# XD.net
KiCad netlist of a schematic drawn in Altium Designer
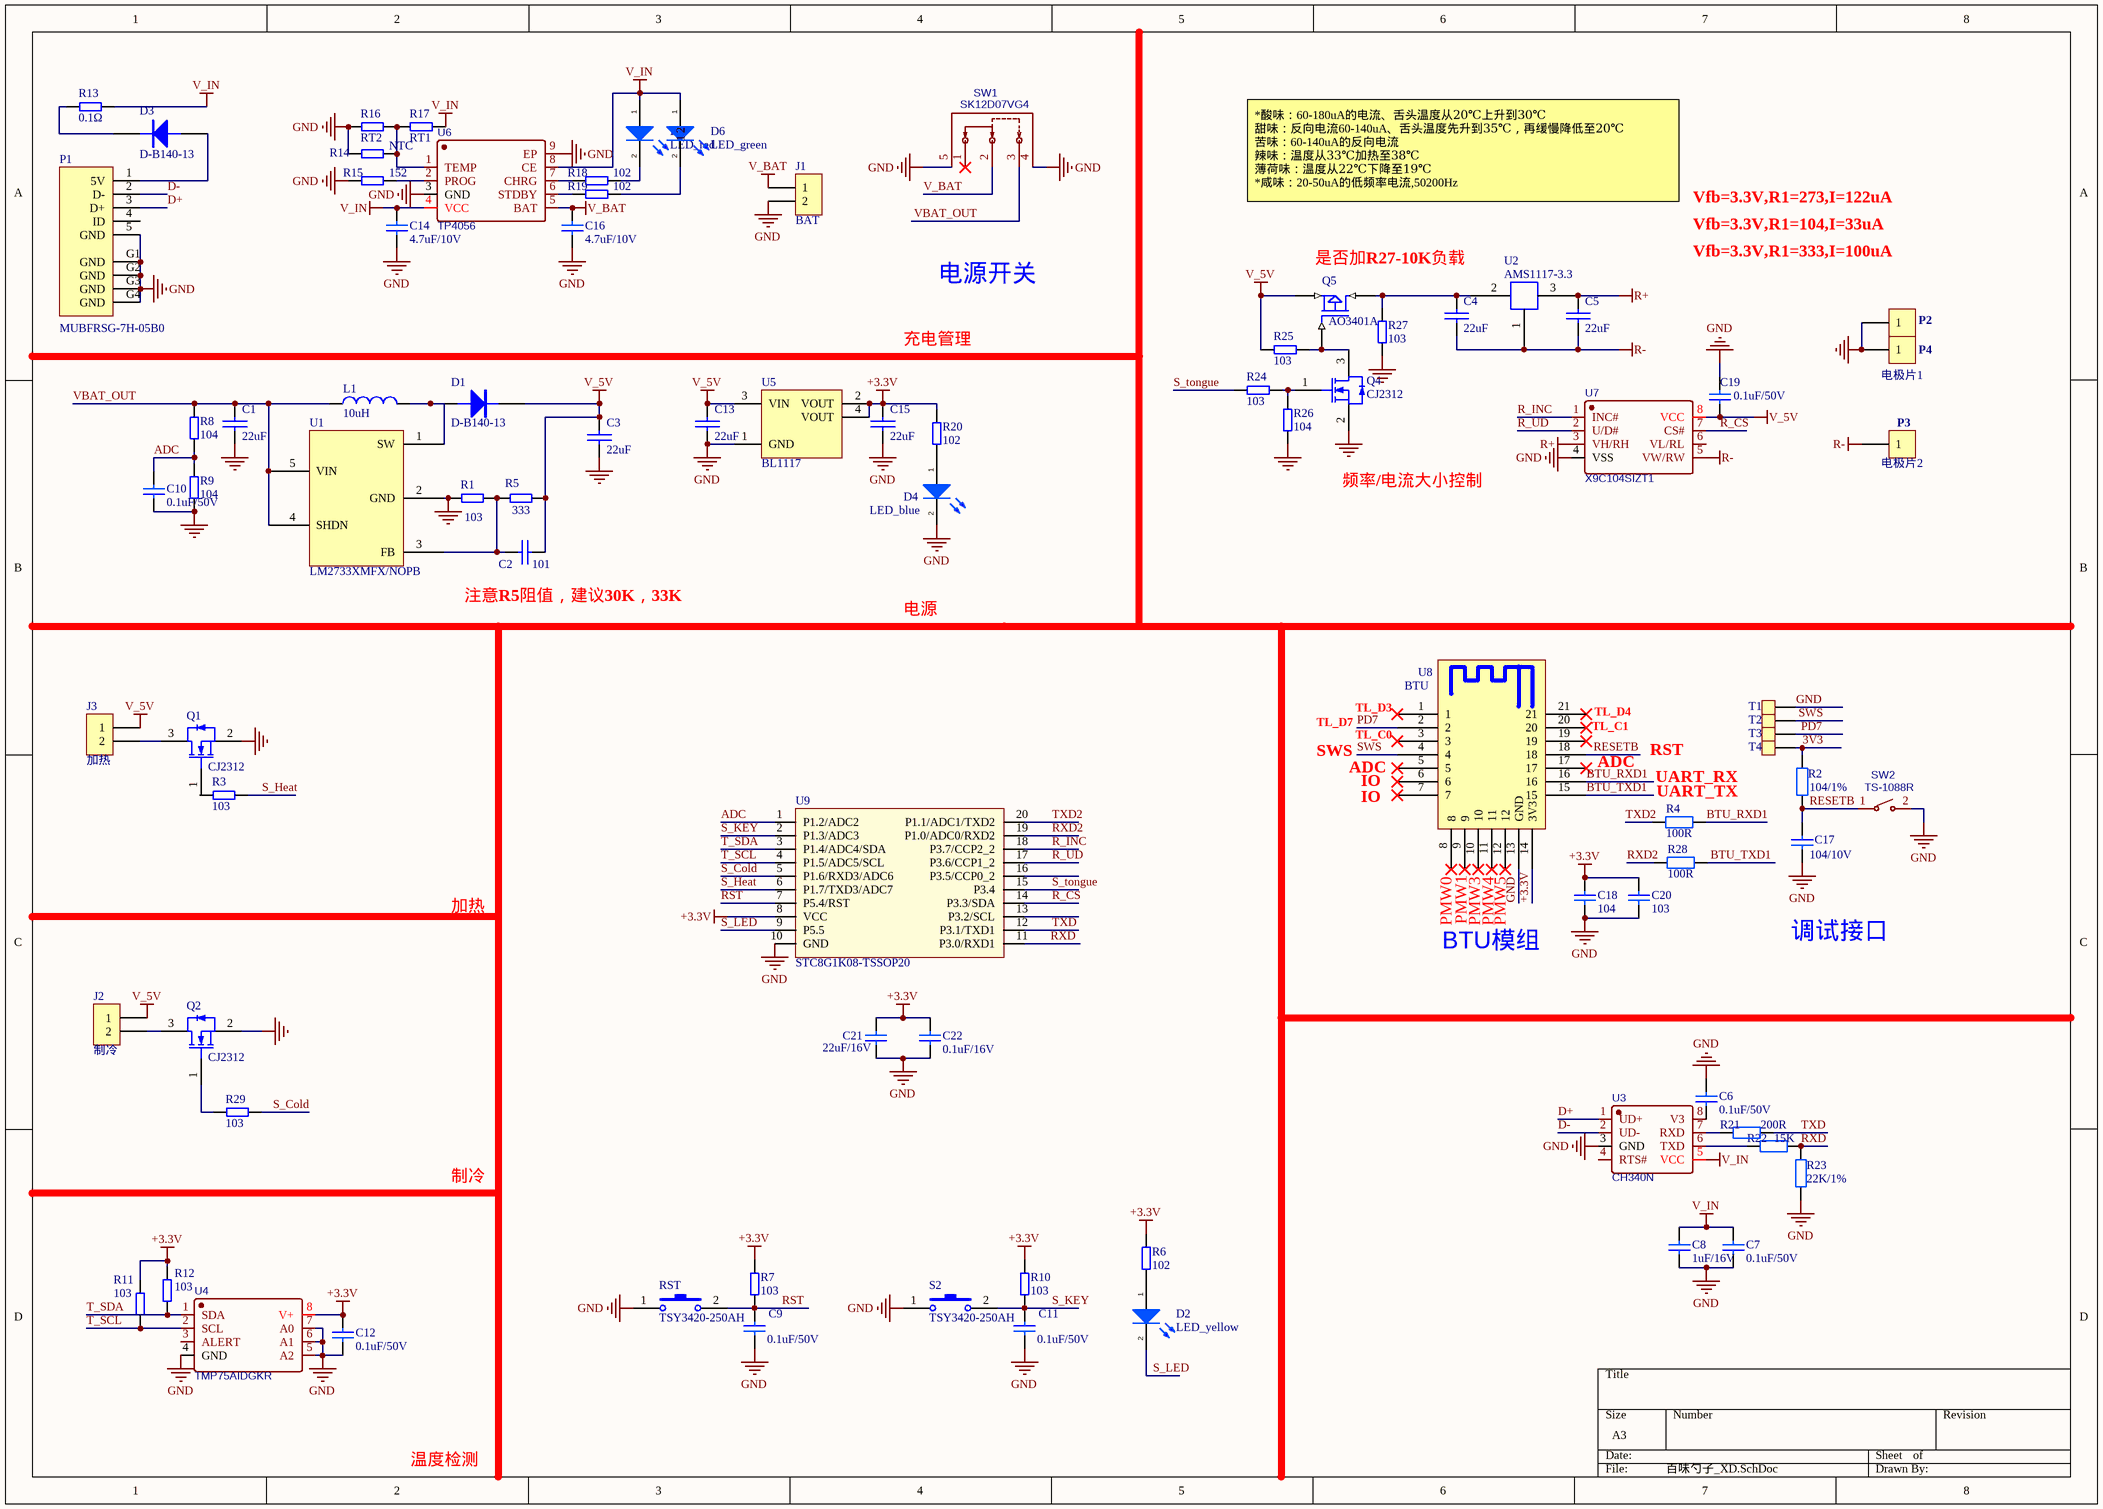
[diagram p0: 百味勺子_XD.SchDoc]

(export (version "E")
  (design (tool "Eeschema 10.0.6"))
  (components
    (comp (ref "C1") (value "22uF") (footprint "C1206") (libsource (lib "altium-import") (part "root_0_C1_")))
    (comp (ref "C2")
      (value "101")
      (footprint "C0603")
      (description "Capacitor")
      (libsource (lib "先锋器件封装库") (part "CAP"))
    )
    (comp (ref "C3") (value "22uF") (footprint "C1206") (libsource (lib "altium-import") (part "root_0_C1_")))
    (comp (ref "C4") (value "22uF") (footprint "C1206") (libsource (lib "altium-import") (part "root_0_C1_")))
    (comp (ref "C5") (value "22uF") (footprint "C1206") (libsource (lib "altium-import") (part "root_0_C1_")))
    (comp (ref "C6")
      (value "0.1uF/50V")
      (footprint "0603_C")
      (description "无极性电容")
      (fields (field (name "PART NUMBER") "1.02.05.00834") (field (name "修改人") "system"))
      (libsource (lib "Database_Libs") (part "Capacitor - non polarized"))
    )
    (comp (ref "C7")
      (value "0.1uF/50V")
      (footprint "0603_C")
      (description "无极性电容")
      (fields (field (name "PART NUMBER") "1.02.05.00834") (field (name "修改人") "system"))
      (libsource (lib "Database_Libs") (part "Capacitor - non polarized"))
    )
    (comp (ref "C8")
      (value "1uF/16V")
      (footprint "0603_C")
      (description "无极性电容")
      (fields (field (name "PART NUMBER") "1.02.03.00181") (field (name "修改人") "system"))
      (libsource (lib "Database_Libs") (part "Capacitor - non polarized"))
    )
    (comp (ref "C9")
      (value "0.1uF/50V")
      (footprint "0603_C")
      (description "无极性电容")
      (fields (field (name "PART NUMBER") "1.02.05.00150") (field (name "修改人") "system"))
      (libsource (lib "Database_Libs") (part "Capacitor - non polarized"))
    )
    (comp (ref "C10")
      (value "0.1uF/50V")
      (footprint "0603_C")
      (description "无极性电容")
      (fields (field (name "PART NUMBER") "1.02.05.00150") (field (name "修改人") "system"))
      (libsource (lib "Database_Libs") (part "Capacitor - non polarized"))
    )
    (comp (ref "C11")
      (value "0.1uF/50V")
      (footprint "0603_C")
      (description "无极性电容")
      (fields (field (name "PART NUMBER") "1.02.05.00150") (field (name "修改人") "system"))
      (libsource (lib "Database_Libs") (part "Capacitor - non polarized"))
    )
    (comp (ref "C12")
      (value "0.1uF/50V")
      (footprint "0603_C")
      (description "无极性电容")
      (fields (field (name "PART NUMBER") "1.02.05.00150") (field (name "修改人") "system"))
      (libsource (lib "Database_Libs") (part "Capacitor - non polarized"))
    )
    (comp (ref "C13")
      (value "22uF")
      (footprint "C1206")
      (libsource (lib "altium-import") (part "root_0_C1_"))
    )
    (comp (ref "C14")
      (value "4.7uF/10V")
      (footprint "0603_C")
      (description "无极性电容")
      (fields (field (name "PART NUMBER") "1.02.05.00710") (field (name "修改人") "system"))
      (libsource (lib "Database_Libs") (part "Capacitor - non polarized"))
    )
    (comp (ref "C15")
      (value "22uF")
      (footprint "C1206")
      (libsource (lib "altium-import") (part "root_0_C1_"))
    )
    (comp (ref "C16")
      (value "4.7uF/10V")
      (footprint "0603_C")
      (description "无极性电容")
      (fields (field (name "PART NUMBER") "1.02.05.00710") (field (name "修改人") "system"))
      (libsource (lib "Database_Libs") (part "Capacitor - non polarized"))
    )
    (comp (ref "C17")
      (value "104/10V")
      (footprint "C0402_GRM15")
      (description "无极性电容")
      (fields (field (name "PART NUMBER") "1.02.05.00869"))
      (libsource (lib "Database_Libs4") (part "Capacitor - non polarized"))
    )
    (comp (ref "C18")
      (value "104")
      (footprint "C0402_GRM15")
      (description "无极性电容")
      (fields (field (name "PART NUMBER") "1.02.05.00869"))
      (libsource (lib "Database_Libs4") (part "Capacitor - non polarized"))
    )
    (comp (ref "C19")
      (value "0.1uF/50V")
      (footprint "0603_C")
      (description "无极性电容")
      (fields (field (name "PART NUMBER") "1.02.05.00150") (field (name "修改人") "system"))
      (libsource (lib "Database_Libs") (part "Capacitor - non polarized"))
    )
    (comp (ref "C20")
      (value "103")
      (footprint "C0402_GRM15")
      (description "无极性电容")
      (fields (field (name "PART NUMBER") "1.02.05.00869"))
      (libsource (lib "Database_Libs4") (part "Capacitor - non polarized"))
    )
    (comp (ref "C21")
      (value "22uF/16V")
      (footprint "C0603")
      (description "无极性电容")
      (fields (field (name "PART NUMBER") "1.02.03.00181") (field (name "修改人") "system"))
      (libsource (lib "Database_Libs") (part "Capacitor - non polarized"))
    )
    (comp (ref "C22")
      (value "0.1uF/16V")
      (footprint "C0402_GRM15")
      (description "无极性电容")
      (fields (field (name "PART NUMBER") "1.02.05.00834") (field (name "修改人") "system"))
      (libsource (lib "Database_Libs") (part "Capacitor - non polarized"))
    )
    (comp (ref "D1")
      (value "D-B140-13")
      (footprint "XF-SS12C")
      (description "Diode")
      (fields (field (name "SPECIFICATION") "D-B140-13"))
      (libsource (lib "先锋器件封装库") (part "DIODE"))
    )
    (comp (ref "D2")
      (value "LED_yellow")
      (footprint "0603_LED_S3")
      (description "LED")
      (fields (field (name "PART NUMBER") "1.06.02.00449") (field (name "修改人") "system"))
      (libsource (lib "Database_Libs") (part "LED"))
    )
    (comp (ref "D3")
      (value "D-B140-13")
      (footprint "XF-SS12C")
      (description "Diode")
      (fields (field (name "SPECIFICATION") "D-B140-13"))
      (libsource (lib "先锋器件封装库") (part "DIODE"))
    )
    (comp (ref "D4")
      (value "LED_blue")
      (footprint "0603_LED_S3")
      (description "LED")
      (fields (field (name "PART NUMBER") "1.06.02.00449") (field (name "修改人") "system"))
      (libsource (lib "Database_Libs") (part "LED"))
    )
    (comp (ref "D5")
      (value "LED_red")
      (footprint "LED0603")
      (description "LED")
      (fields (field (name "PART NUMBER") "1.06.02.00449") (field (name "修改人") "system"))
      (libsource (lib "Database_Libs") (part "LED"))
    )
    (comp (ref "D6")
      (value "LED_green")
      (footprint "LED0603")
      (description "LED")
      (fields (field (name "PART NUMBER") "1.06.02.00449") (field (name "修改人") "system"))
      (libsource (lib "") (part "LED_1"))
    )
    (comp (ref "J1")
      (value "BAT")
      (footprint "SIP02")
      (description "Connector")
      (libsource (lib "altium-import") (part "root_0_CON2_"))
    )
    (comp (ref "J2")
      (value "制冷")
      (footprint "HDR1X2")
      (description "Connector")
      (libsource (lib "接插件") (part "CON2"))
    )
    (comp (ref "J3")
      (value "加热")
      (footprint "HDR1X2")
      (description "Connector")
      (libsource (lib "接插件") (part "CON2"))
    )
    (comp (ref "L1")
      (value "10uH")
      (footprint "CD73")
      (description "Inductor")
      (fields (field (name "Comment") "4.7uH") (field (name "PUBLISHER") "Altium Limited"))
      (libsource (lib "altium-import") (part "root_0_Inductor_"))
    )
    (comp (ref "P1")
      (value "MUBFRSG-7H-05B0")
      (footprint "MIRCOUSB_5PIN-A")
      (description "USB")
      (fields (field (name "PART NUMBER") "1.16.99.00399") (field (name "修改人") "system"))
      (libsource (lib "Database_Libs") (part "USB_5p"))
    )
    (comp (ref "P2") (value "CON1") (footprint "焊点1") (libsource (lib "智能烧水壶 -电源板") (part "CON1")))
    (comp (ref "P3") (value "CON1") (footprint "焊点1") (libsource (lib "智能烧水壶 -电源板") (part "CON1")))
    (comp (ref "P4") (value "CON1") (footprint "焊点1") (libsource (lib "智能烧水壶 -电源板") (part "CON1")))
    (comp (ref "Q1")
      (value "CJ2312")
      (footprint "SOT23-3")
      (description "N-Channel MOSFET")
      (fields
        (field (name "PART NUMBER") "1.06.11.00008")
        (field (name "ORCAD LIBRARY PATH") "‪Z:\\tuya_lib\\sch-lib\\DISCRETE.OLB")
        (field (name "修改人") "system")
      )
      (libsource (lib "Database_Libs") (part "MOSFET-N"))
    )
    (comp (ref "Q2")
      (value "CJ2312")
      (footprint "SOT23-3")
      (description "N-Channel MOSFET")
      (fields
        (field (name "PART NUMBER") "1.06.11.00008")
        (field (name "ORCAD LIBRARY PATH") "‪Z:\\tuya_lib\\sch-lib\\DISCRETE.OLB")
        (field (name "修改人") "system")
      )
      (libsource (lib "Database_Libs") (part "MOSFET-N"))
    )
    (comp (ref "Q4")
      (value "CJ2312")
      (footprint "SOT23-3")
      (description "N-Channel MOSFET")
      (fields
        (field (name "PART NUMBER") "1.06.11.00008")
        (field (name "ORCAD LIBRARY PATH") "‪Z:\\tuya_lib\\sch-lib\\DISCRETE.OLB")
        (field (name "修改人") "system")
      )
      (libsource (lib "Database_Libs") (part "MOSFET-N"))
    )
    (comp (ref "Q5")
      (value "AO3401A")
      (footprint "SOT-23")
      (description "MOSFET-P")
      (fields (field (name "SPECIFICATION") "AO3401A"))
      (libsource (lib "先锋器件封装库") (part "MOSFET-P"))
    )
    (comp (ref "R1")
      (value "103")
      (footprint "0603_R")
      (description "RES")
      (libsource (lib "先锋器件封装库") (part "RES-1"))
    )
    (comp (ref "R2")
      (value "104/1%")
      (footprint "R0402")
      (description "电阻")
      (fields (field (name "PART NUMBER") "1.01.01.00808"))
      (libsource (lib "") (part "Resistor_1"))
    )
    (comp (ref "R3")
      (value "103")
      (footprint "0603_R")
      (description "RES")
      (libsource (lib "先锋器件封装库") (part "RES-1"))
    )
    (comp (ref "R4")
      (value "100R")
      (footprint "R0402")
      (description "电阻")
      (fields (field (name "PART NUMBER") "1.01.01.00808"))
      (libsource (lib "Database_Libs4") (part "Resistor"))
    )
    (comp (ref "R5")
      (value "333")
      (footprint "0603_R")
      (description "RES")
      (libsource (lib "先锋器件封装库") (part "RES-1"))
    )
    (comp (ref "R6")
      (value "102")
      (footprint "0603_R")
      (description "RES")
      (libsource (lib "先锋器件封装库") (part "RES-1"))
    )
    (comp (ref "R7")
      (value "103")
      (footprint "0603_R")
      (description "RES")
      (libsource (lib "先锋器件封装库") (part "RES-1"))
    )
    (comp (ref "R8")
      (value "104")
      (footprint "0603_R")
      (description "RES")
      (libsource (lib "先锋器件封装库") (part "RES-1"))
    )
    (comp (ref "R9")
      (value "104")
      (footprint "0603_R")
      (description "RES")
      (libsource (lib "先锋器件封装库") (part "RES-1"))
    )
    (comp (ref "R10")
      (value "103")
      (footprint "0603_R")
      (description "RES")
      (libsource (lib "先锋器件封装库") (part "RES-1"))
    )
    (comp (ref "R11")
      (value "103")
      (footprint "0603_R")
      (description "RES")
      (libsource (lib "先锋器件封装库") (part "RES-1"))
    )
    (comp (ref "R12")
      (value "103")
      (footprint "0603_R")
      (description "RES")
      (libsource (lib "先锋器件封装库") (part "RES-1"))
    )
    (comp (ref "R13")
      (value "0.1Ω")
      (footprint "0603_R")
      (description "RES")
      (libsource (lib "先锋器件封装库") (part "RES-1"))
    )
    (comp (ref "R14")
      (value "NTC")
      (footprint "0603_R")
      (description "RES")
      (libsource (lib "先锋器件封装库") (part "RES-1"))
    )
    (comp (ref "R15")
      (value "152")
      (footprint "0603_R")
      (description "RES")
      (libsource (lib "先锋器件封装库") (part "RES-1"))
    )
    (comp (ref "R16")
      (value "RT2")
      (footprint "0603_R")
      (description "RES")
      (libsource (lib "先锋器件封装库") (part "RES-1"))
    )
    (comp (ref "R17")
      (value "RT1")
      (footprint "0603_R")
      (description "RES")
      (libsource (lib "先锋器件封装库") (part "RES-1"))
    )
    (comp (ref "R18")
      (value "102")
      (footprint "0603_R")
      (description "RES")
      (libsource (lib "先锋器件封装库") (part "RES-1"))
    )
    (comp (ref "R19")
      (value "102")
      (footprint "0603_R")
      (description "RES")
      (libsource (lib "先锋器件封装库") (part "RES-1"))
    )
    (comp (ref "R20")
      (value "102")
      (footprint "0603_R")
      (description "RES")
      (libsource (lib "先锋器件封装库") (part "RES-1"))
    )
    (comp (ref "R21")
      (value "200R")
      (footprint "0603_R")
      (description "电阻")
      (fields (field (name "PART NUMBER") "1.01.01.00808") (field (name "修改人") "system"))
      (libsource (lib "") (part "Resistor_1"))
    )
    (comp (ref "R22")
      (value "15K")
      (footprint "0603_R")
      (description "电阻")
      (fields (field (name "PART NUMBER") "1.01.01.01301") (field (name "修改人") "system"))
      (libsource (lib "") (part "Resistor_1"))
    )
    (comp (ref "R23")
      (value "22K/1%")
      (footprint "0603_R")
      (description "电阻")
      (fields (field (name "PART NUMBER") "1.01.01.01030") (field (name "修改人") "system"))
      (libsource (lib "Database_Libs") (part "Resistor"))
    )
    (comp (ref "R24")
      (value "103")
      (footprint "0603_R")
      (description "RES")
      (libsource (lib "先锋器件封装库") (part "RES-1"))
    )
    (comp (ref "R25")
      (value "103")
      (footprint "0603_R")
      (description "RES")
      (libsource (lib "先锋器件封装库") (part "RES-1"))
    )
    (comp (ref "R26")
      (value "104")
      (footprint "0603_R")
      (description "RES")
      (libsource (lib "先锋器件封装库") (part "RES-1"))
    )
    (comp (ref "R27")
      (value "103")
      (footprint "0603_R")
      (description "RES")
      (libsource (lib "先锋器件封装库") (part "RES-1"))
    )
    (comp (ref "R28")
      (value "100R")
      (footprint "R0402")
      (description "电阻")
      (fields (field (name "PART NUMBER") "1.01.01.00808"))
      (libsource (lib "Database_Libs4") (part "Resistor"))
    )
    (comp (ref "R29")
      (value "103")
      (footprint "0603_R")
      (description "RES")
      (libsource (lib "先锋器件封装库") (part "RES-1"))
    )
    (comp (ref "RST")
      (value "TSY3420-250AH")
      (footprint "SW-PB2_SMT-3X4")
      (description "2pin轻触开关（无固定脚）")
      (fields (field (name "PART NUMBER") "1.13.04.00024") (field (name "修改人") "system"))
      (libsource (lib "Database_Libs") (part "SW-PB2"))
    )
    (comp (ref "S2")
      (value "TSY3420-250AH")
      (footprint "SW-PB2_SMT-3X4")
      (description "2pin轻触开关（无固定脚）")
      (fields (field (name "PART NUMBER") "1.13.04.00024") (field (name "修改人") "system"))
      (libsource (lib "Database_Libs") (part "SW-PB2"))
    )
    (comp (ref "SW1")
      (value "SK12D07VG4")
      (footprint "SK12D07VG4")
      (fields (field (name "BOM_SUPPLIER PART") "C393937") (field (name "CONTRIBUTOR") "LCSC"))
      (libsource (lib "altium-import") (part "root_0_SK12D07VG4_"))
    )
    (comp (ref "SW2")
      (value "TS-1088R")
      (footprint "TS-1088R-02026")
      (fields
        (field (name "BOM_SUPPLIER PART") "C455280")
        (field (name "BOM_MANUFACTURER PART") "TS-1088R-02026")
        (field (name "CONTRIBUTOR") "LCSC")
      )
      (libsource (lib "altium-import") (part "root_0_TS-1088R-02026_"))
    )
    (comp (ref "T1") (value "TP") (footprint "TP1") (libsource (lib "MIAXIS-SCH") (part "TP")))
    (comp (ref "T2") (value "TP") (footprint "TP1") (libsource (lib "MIAXIS-SCH") (part "TP")))
    (comp (ref "T3") (value "TP") (footprint "TP1") (libsource (lib "MIAXIS-SCH") (part "TP")))
    (comp (ref "T4") (value "TP") (footprint "TP1") (libsource (lib "MIAXIS-SCH") (part "TP")))
    (comp (ref "U1")
      (value "LM2733XMFX/NOPB")
      (footprint "SOT23-5")
      (description "LM2733")
      (fields (field (name "SPECIFICATION") "LM2733XMFX/NOPB"))
      (libsource (lib "先锋器件封装库") (part "LM2733"))
    )
    (comp (ref "U2") (value "AMS1117-3.3") (footprint "SOT-89C") (libsource (lib "*") (part "WYK")))
    (comp (ref "U3")
      (value "CH340N")
      (footprint "SOP-8")
      (fields (field (name "BOM_SUPPLIER PART") "C506813") (field (name "CONTRIBUTOR") "LCSC"))
      (libsource (lib "TY") (part "CH340N"))
    )
    (comp (ref "U4")
      (value "TMP75AIDGKR")
      (footprint "VSSOP-8_L3.0-W3.0-P0.65-LS5.0-BL")
      (fields (field (name "BOM_SUPPLIER PART") "C105258") (field (name "CONTRIBUTOR") "LCSC"))
      (libsource (lib "TY") (part "TMP75AIDGKR"))
    )
    (comp (ref "U5")
      (value "BL1117")
      (footprint "SOT-223")
      (description "线性稳压源")
      (fields (field (name "PART NUMBER") "1.05.99.00236") (field (name "修改人") "system"))
      (libsource (lib "Database_Libs") (part "LDO_REG1117"))
    )
    (comp (ref "U6")
      (value "TP4056")
      (footprint "ESOP-8")
      (fields (field (name "BOM_SUPPLIER PART") "C725790") (field (name "CONTRIBUTOR") "LCSC"))
      (libsource (lib "TY") (part "TP4056_C725790"))
    )
    (comp (ref "U7")
      (value "X9C104SIZT1")
      (footprint "SOIC-8_L4.9-W3.9-P1.27-LS6.0-BL")
      (fields (field (name "BOM_SUPPLIER PART") "C11979"))
      (libsource (lib "TY") (part "X9C104SIZT1"))
    )
    (comp (ref "U8")
      (value "BTU")
      (footprint "CBU1")
      (fields (field (name "PART NUMBER") "0110"))
      (libsource (lib "BTU_V100") (part "CBU"))
    )
    (comp (ref "U9")
      (value "STC8G1K08-TSSOP20")
      (footprint "SOP-20_300mil")
      (libsource (lib "百味勺子_XD") (part "STC8G1K08-TSSOP20"))
    )
  )
  (nets
    (net (code "1") (name "+3.3V") (class "Default")
      (node (ref "C12") (pin "1") (pinfunction "1_1") (pintype "passive"))
      (node (ref "C15") (pin "1") (pinfunction "1_1") (pintype "passive"))
      (node (ref "C18") (pin "1") (pinfunction "1_1") (pintype "passive"))
      (node (ref "C20") (pin "1") (pinfunction "1_1") (pintype "passive"))
      (node (ref "C21") (pin "2") (pinfunction "2_2") (pintype "passive"))
      (node (ref "C22") (pin "2") (pinfunction "2_2") (pintype "passive"))
      (node (ref "R10") (pin "2") (pintype "passive"))
      (node (ref "R11") (pin "2") (pintype "passive"))
      (node (ref "R12") (pin "2") (pintype "passive"))
      (node (ref "R20") (pin "2") (pintype "passive"))
      (node (ref "R6") (pin "1") (pintype "passive"))
      (node (ref "R7") (pin "2") (pintype "passive"))
      (node (ref "U4") (pin "8") (pinfunction "V+_8") (pintype "passive"))
      (node (ref "U5") (pin "2") (pinfunction "VOUT_2") (pintype "passive"))
      (node (ref "U5") (pin "4") (pinfunction "VOUT_4") (pintype "passive"))
      (node (ref "U8") (pin "14") (pinfunction "3V3_14") (pintype "passive"))
      (node (ref "U9") (pin "8") (pinfunction "VCC_8") (pintype "passive"))
    )
    (net (code "2") (name "/3V3") (class "Default")
      (node (ref "R2") (pin "2") (pinfunction "2_2") (pintype "passive"))
      (node (ref "T4") (pin "1") (pinfunction "1_1") (pintype "passive"))
    )
    (net (code "3") (name "/ADC") (class "Default")
      (node (ref "C10") (pin "2") (pinfunction "2_2") (pintype "passive"))
      (node (ref "R8") (pin "1") (pintype "passive"))
      (node (ref "R9") (pin "2") (pintype "passive"))
      (node (ref "U9") (pin "1") (pinfunction "P1.2/ADC2_1") (pintype "passive"))
    )
    (net (code "4") (name "/BTU_RXD1") (class "Default")
      (node (ref "R4") (pin "1") (pinfunction "1_1") (pintype "passive"))
      (node (ref "U8") (pin "16") (pinfunction "16_16") (pintype "passive"))
    )
    (net (code "5") (name "/BTU_TXD1") (class "Default")
      (node (ref "R28") (pin "1") (pinfunction "1_1") (pintype "passive"))
      (node (ref "U8") (pin "15") (pinfunction "15_15") (pintype "passive"))
    )
    (net (code "6") (name "/D+") (class "Default")
      (node (ref "P1") (pin "3") (pinfunction "D+_3") (pintype "passive"))
      (node (ref "U3") (pin "1") (pinfunction "UD+_1") (pintype "passive"))
    )
    (net (code "7") (name "/D-") (class "Default")
      (node (ref "P1") (pin "2") (pinfunction "D-_2") (pintype "passive"))
      (node (ref "U3") (pin "2") (pinfunction "UD-_2") (pintype "passive"))
    )
    (net (code "8") (name "/PD7") (class "Default")
      (node (ref "T3") (pin "1") (pinfunction "1_1") (pintype "passive"))
      (node (ref "U8") (pin "2") (pinfunction "2_2") (pintype "passive"))
    )
    (net (code "9") (name "/RESETB") (class "Default")
      (node (ref "C17") (pin "1") (pinfunction "1_1") (pintype "passive"))
      (node (ref "R2") (pin "1") (pinfunction "1_1") (pintype "passive"))
      (node (ref "SW2") (pin "1") (pinfunction "1_1") (pintype "passive"))
      (node (ref "U8") (pin "18") (pinfunction "18_18") (pintype "passive"))
    )
    (net (code "10") (name "/RST") (class "Default")
      (node (ref "C9") (pin "1") (pinfunction "1_1") (pintype "passive"))
      (node (ref "R7") (pin "1") (pintype "passive"))
      (node (ref "RST") (pin "2") (pinfunction "2_2") (pintype "passive"))
      (node (ref "U9") (pin "7") (pinfunction "P5.4/RST_7") (pintype "passive"))
    )
    (net (code "11") (name "/RXD") (class "Default")
      (node (ref "R22") (pin "2") (pinfunction "2_2") (pintype "passive"))
      (node (ref "R23") (pin "2") (pinfunction "2_2") (pintype "passive"))
      (node (ref "U9") (pin "11") (pinfunction "P3.0/RXD1_11") (pintype "passive"))
    )
    (net (code "12") (name "/RXD2") (class "Default")
      (node (ref "R28") (pin "2") (pinfunction "2_2") (pintype "passive"))
      (node (ref "U9") (pin "19") (pinfunction "P1.0/ADC0/RXD2_19") (pintype "passive"))
    )
    (net (code "13") (name "/R_CS") (class "Default")
      (node (ref "U7") (pin "7") (pinfunction "CS#_7") (pintype "passive"))
      (node (ref "U9") (pin "14") (pinfunction "P3.3/SDA_14") (pintype "passive"))
    )
    (net (code "14") (name "/R_INC") (class "Default")
      (node (ref "U7") (pin "1") (pinfunction "INC#_1") (pintype "passive"))
      (node (ref "U9") (pin "18") (pinfunction "P3.7/CCP2_2_18") (pintype "passive"))
    )
    (net (code "15") (name "/R_UD") (class "Default")
      (node (ref "U7") (pin "2") (pinfunction "U/D#_2") (pintype "passive"))
      (node (ref "U9") (pin "17") (pinfunction "P3.6/CCP1_2_17") (pintype "passive"))
    )
    (net (code "16") (name "/SWS") (class "Default")
      (node (ref "T2") (pin "1") (pinfunction "1_1") (pintype "passive"))
      (node (ref "U8") (pin "4") (pinfunction "4_4") (pintype "passive"))
    )
    (net (code "17") (name "/S_Cold") (class "Default")
      (node (ref "R29") (pin "1") (pintype "passive"))
      (node (ref "U9") (pin "5") (pinfunction "P1.6/RXD3/ADC6_5") (pintype "passive"))
    )
    (net (code "18") (name "/S_Heat") (class "Default")
      (node (ref "R3") (pin "1") (pintype "passive"))
      (node (ref "U9") (pin "6") (pinfunction "P1.7/TXD3/ADC7_6") (pintype "passive"))
    )
    (net (code "19") (name "/S_KEY") (class "Default")
      (node (ref "C11") (pin "1") (pinfunction "1_1") (pintype "passive"))
      (node (ref "R10") (pin "1") (pintype "passive"))
      (node (ref "S2") (pin "2") (pinfunction "2_2") (pintype "passive"))
      (node (ref "U9") (pin "2") (pinfunction "P1.3/ADC3_2") (pintype "passive"))
    )
    (net (code "20") (name "/S_LED") (class "Default")
      (node (ref "D2") (pin "2") (pinfunction "2_2") (pintype "passive"))
      (node (ref "U9") (pin "9") (pinfunction "P5.5_9") (pintype "passive"))
    )
    (net (code "21") (name "/S_tongue") (class "Default")
      (node (ref "R24") (pin "1") (pintype "passive"))
      (node (ref "U9") (pin "15") (pinfunction "P3.4_15") (pintype "passive"))
    )
    (net (code "22") (name "/TXD") (class "Default")
      (node (ref "R21") (pin "2") (pinfunction "2_2") (pintype "passive"))
      (node (ref "U9") (pin "12") (pinfunction "P3.1/TXD1_12") (pintype "passive"))
    )
    (net (code "23") (name "/TXD2") (class "Default")
      (node (ref "R4") (pin "2") (pinfunction "2_2") (pintype "passive"))
      (node (ref "U9") (pin "20") (pinfunction "P1.1/ADC1/TXD2_20") (pintype "passive"))
    )
    (net (code "24") (name "/T_SCL") (class "Default")
      (node (ref "R11") (pin "1") (pintype "passive"))
      (node (ref "U4") (pin "2") (pinfunction "SCL_2") (pintype "passive"))
      (node (ref "U9") (pin "4") (pinfunction "P1.5/ADC5/SCL_4") (pintype "passive"))
    )
    (net (code "25") (name "/T_SDA") (class "Default")
      (node (ref "R12") (pin "1") (pintype "passive"))
      (node (ref "U4") (pin "1") (pinfunction "SDA_1") (pintype "passive"))
      (node (ref "U9") (pin "3") (pinfunction "P1.4/ADC4/SDA_3") (pintype "passive"))
    )
    (net (code "26") (name "/VBAT_OUT") (class "Default")
      (node (ref "C1") (pin "1") (pinfunction "1_1") (pintype "passive"))
      (node (ref "L1") (pin "1") (pinfunction "1_1") (pintype "passive"))
      (node (ref "R8") (pin "2") (pintype "passive"))
      (node (ref "SW1") (pin "3") (pinfunction "3_3") (pintype "passive"))
      (node (ref "U1") (pin "4") (pinfunction "SHDN_4") (pintype "passive"))
      (node (ref "U1") (pin "5") (pinfunction "VIN_5") (pintype "passive"))
    )
    (net (code "27") (name "GND") (class "Default")
      (node (ref "C1") (pin "2") (pinfunction "2_2") (pintype "passive"))
      (node (ref "C10") (pin "1") (pinfunction "1_1") (pintype "passive"))
      (node (ref "C11") (pin "2") (pinfunction "2_2") (pintype "passive"))
      (node (ref "C12") (pin "2") (pinfunction "2_2") (pintype "passive"))
      (node (ref "C13") (pin "2") (pinfunction "2_2") (pintype "passive"))
      (node (ref "C14") (pin "1") (pinfunction "1_1") (pintype "passive"))
      (node (ref "C15") (pin "2") (pinfunction "2_2") (pintype "passive"))
      (node (ref "C16") (pin "1") (pinfunction "1_1") (pintype "passive"))
      (node (ref "C17") (pin "2") (pinfunction "2_2") (pintype "passive"))
      (node (ref "C18") (pin "2") (pinfunction "2_2") (pintype "passive"))
      (node (ref "C19") (pin "2") (pinfunction "2_2") (pintype "passive"))
      (node (ref "C20") (pin "2") (pinfunction "2_2") (pintype "passive"))
      (node (ref "C21") (pin "1") (pinfunction "1_1") (pintype "passive"))
      (node (ref "C22") (pin "1") (pinfunction "1_1") (pintype "passive"))
      (node (ref "C3") (pin "2") (pinfunction "2_2") (pintype "passive"))
      (node (ref "C6") (pin "2") (pinfunction "2_2") (pintype "passive"))
      (node (ref "C7") (pin "1") (pinfunction "1_1") (pintype "passive"))
      (node (ref "C8") (pin "1") (pinfunction "1_1") (pintype "passive"))
      (node (ref "C9") (pin "2") (pinfunction "2_2") (pintype "passive"))
      (node (ref "D4") (pin "2") (pinfunction "2_2") (pintype "passive"))
      (node (ref "J1") (pin "2") (pinfunction "2_2") (pintype "passive"))
      (node (ref "P1") (pin "5") (pinfunction "GND_5") (pintype "passive"))
      (node (ref "P1") (pin "G1") (pinfunction "GND_G1") (pintype "passive"))
      (node (ref "P1") (pin "G2") (pinfunction "GND_G2") (pintype "passive"))
      (node (ref "P1") (pin "G3") (pinfunction "GND_G3") (pintype "passive"))
      (node (ref "P1") (pin "G4") (pinfunction "GND_G4") (pintype "passive"))
      (node (ref "P2") (pin "1") (pinfunction "1_1") (pintype "passive"))
      (node (ref "P4") (pin "1") (pinfunction "1_1") (pintype "passive"))
      (node (ref "Q1") (pin "2") (pinfunction "S_2") (pintype "passive"))
      (node (ref "Q2") (pin "2") (pinfunction "S_2") (pintype "passive"))
      (node (ref "Q4") (pin "2") (pinfunction "S_2") (pintype "passive"))
      (node (ref "R1") (pin "1") (pintype "passive"))
      (node (ref "R14") (pin "2") (pintype "passive"))
      (node (ref "R15") (pin "2") (pintype "passive"))
      (node (ref "R16") (pin "1") (pintype "passive"))
      (node (ref "R23") (pin "1") (pinfunction "1_1") (pintype "passive"))
      (node (ref "R26") (pin "1") (pintype "passive"))
      (node (ref "R27") (pin "1") (pintype "passive"))
      (node (ref "R9") (pin "1") (pintype "passive"))
      (node (ref "RST") (pin "1") (pinfunction "1_1") (pintype "passive"))
      (node (ref "S2") (pin "1") (pinfunction "1_1") (pintype "passive"))
      (node (ref "SW1") (pin "4") (pinfunction "4_4") (pintype "passive"))
      (node (ref "SW1") (pin "5") (pinfunction "5_5") (pintype "passive"))
      (node (ref "SW2") (pin "2") (pinfunction "2_2") (pintype "passive"))
      (node (ref "T1") (pin "1") (pinfunction "1_1") (pintype "passive"))
      (node (ref "U1") (pin "2") (pinfunction "GND_2") (pintype "passive"))
      (node (ref "U3") (pin "3") (pinfunction "GND_3") (pintype "passive"))
      (node (ref "U4") (pin "4") (pinfunction "GND_4") (pintype "passive"))
      (node (ref "U4") (pin "5") (pinfunction "A2_5") (pintype "passive"))
      (node (ref "U4") (pin "6") (pinfunction "A1_6") (pintype "passive"))
      (node (ref "U4") (pin "7") (pinfunction "A0_7") (pintype "passive"))
      (node (ref "U5") (pin "1") (pinfunction "GND_1") (pintype "passive"))
      (node (ref "U6") (pin "3") (pinfunction "GND_3") (pintype "passive"))
      (node (ref "U6") (pin "9") (pinfunction "EP_9") (pintype "passive"))
      (node (ref "U7") (pin "4") (pinfunction "VSS_4") (pintype "passive"))
      (node (ref "U8") (pin "13") (pinfunction "GND_13") (pintype "passive"))
      (node (ref "U9") (pin "10") (pinfunction "GND_10") (pintype "passive"))
    )
    (net (code "28") (name "Net-(C4-Pad1)") (class "Default")
      (node (ref "C4") (pin "1") (pinfunction "1_1") (pintype "passive"))
      (node (ref "Q5") (pin "D") (pinfunction "D_D") (pintype "input"))
      (node (ref "R27") (pin "2") (pintype "passive"))
      (node (ref "U2") (pin "2") (pintype "passive"))
    )
    (net (code "29") (name "Net-(D2-Pad1)") (class "Default")
      (node (ref "D2") (pin "1") (pinfunction "1_1") (pintype "passive"))
      (node (ref "R6") (pin "2") (pintype "passive"))
    )
    (net (code "30") (name "Net-(D3-PadK)") (class "Default")
      (node (ref "D3") (pin "K") (pinfunction "K_K") (pintype "passive"))
      (node (ref "R13") (pin "2") (pintype "passive"))
    )
    (net (code "31") (name "Net-(D4-Pad1)") (class "Default")
      (node (ref "D4") (pin "1") (pinfunction "1_1") (pintype "passive"))
      (node (ref "R20") (pin "1") (pintype "passive"))
    )
    (net (code "32") (name "Net-(D5-Pad2)") (class "Default")
      (node (ref "D5") (pin "2") (pinfunction "2_2") (pintype "passive"))
      (node (ref "R18") (pin "2") (pintype "passive"))
    )
    (net (code "33") (name "Net-(D6-Pad2)") (class "Default")
      (node (ref "D6") (pin "2") (pinfunction "2_2") (pintype "passive"))
      (node (ref "R19") (pin "1") (pintype "passive"))
    )
    (net (code "34") (name "Net-(P1-5V)") (class "Default")
      (node (ref "D3") (pin "A") (pinfunction "A_A") (pintype "passive"))
      (node (ref "P1") (pin "1") (pinfunction "5V_1") (pintype "passive"))
    )
    (net (code "35") (name "Net-(Q1-D)") (class "Default")
      (node (ref "J3") (pin "2") (pinfunction "2_2") (pintype "passive"))
      (node (ref "Q1") (pin "3") (pinfunction "D_3") (pintype "passive"))
    )
    (net (code "36") (name "Net-(Q2-D)") (class "Default")
      (node (ref "J2") (pin "2") (pinfunction "2_2") (pintype "passive"))
      (node (ref "Q2") (pin "3") (pinfunction "D_3") (pintype "passive"))
    )
    (net (code "37") (name "Net-(Q2-G)") (class "Default")
      (node (ref "Q2") (pin "1") (pinfunction "G_1") (pintype "passive"))
      (node (ref "R29") (pin "2") (pintype "passive"))
    )
    (net (code "38") (name "Net-(Q4-D)") (class "Default")
      (node (ref "Q4") (pin "3") (pinfunction "D_3") (pintype "passive"))
      (node (ref "Q5") (pin "G") (pinfunction "G_G") (pintype "input"))
      (node (ref "R25") (pin "2") (pintype "passive"))
    )
    (net (code "39") (name "Net-(Q4-G)") (class "Default")
      (node (ref "Q4") (pin "1") (pinfunction "G_1") (pintype "passive"))
      (node (ref "R24") (pin "2") (pintype "passive"))
      (node (ref "R26") (pin "2") (pintype "passive"))
    )
    (net (code "40") (name "Net-(U1-FB)") (class "Default")
      (node (ref "C2") (pin "2") (pinfunction "2_2") (pintype "passive"))
      (node (ref "R1") (pin "2") (pintype "passive"))
      (node (ref "R5") (pin "2") (pintype "passive"))
      (node (ref "U1") (pin "3") (pinfunction "FB_3") (pintype "passive"))
    )
    (net (code "41") (name "Net-(U1-SW)") (class "Default")
      (node (ref "D1") (pin "A") (pinfunction "A_A") (pintype "passive"))
      (node (ref "L1") (pin "2") (pinfunction "2_2") (pintype "passive"))
      (node (ref "U1") (pin "1") (pinfunction "SW_1") (pintype "passive"))
    )
    (net (code "42") (name "Net-(U3-RXD)") (class "Default")
      (node (ref "R21") (pin "1") (pinfunction "1_1") (pintype "passive"))
      (node (ref "U3") (pin "7") (pinfunction "RXD_7") (pintype "passive"))
    )
    (net (code "43") (name "Net-(U3-TXD)") (class "Default")
      (node (ref "R22") (pin "1") (pinfunction "1_1") (pintype "passive"))
      (node (ref "U3") (pin "6") (pinfunction "TXD_6") (pintype "passive"))
    )
    (net (code "44") (name "Net-(U3-V3)") (class "Default")
      (node (ref "C6") (pin "1") (pinfunction "1_1") (pintype "passive"))
      (node (ref "U3") (pin "8") (pinfunction "V3_8") (pintype "passive"))
    )
    (net (code "45") (name "Net-(U6-CHRG)") (class "Default")
      (node (ref "R18") (pin "1") (pintype "passive"))
      (node (ref "U6") (pin "7") (pinfunction "CHRG_7") (pintype "passive"))
    )
    (net (code "46") (name "Net-(U6-PROG)") (class "Default")
      (node (ref "R15") (pin "1") (pintype "passive"))
      (node (ref "U6") (pin "2") (pinfunction "PROG_2") (pintype "passive"))
    )
    (net (code "47") (name "Net-(U6-STDBY)") (class "Default")
      (node (ref "R19") (pin "2") (pintype "passive"))
      (node (ref "U6") (pin "6") (pinfunction "STDBY_6") (pintype "passive"))
    )
    (net (code "48") (name "Net-(U6-TEMP)") (class "Default")
      (node (ref "R14") (pin "1") (pintype "passive"))
      (node (ref "R16") (pin "2") (pintype "passive"))
      (node (ref "R17") (pin "2") (pintype "passive"))
      (node (ref "U6") (pin "1") (pinfunction "TEMP_1") (pintype "passive"))
    )
    (net (code "49") (name "R+") (class "Default")
      (node (ref "C5") (pin "1") (pinfunction "1_1") (pintype "passive"))
      (node (ref "U2") (pin "3") (pintype "passive"))
      (node (ref "U7") (pin "3") (pinfunction "VH/RH_3") (pintype "passive"))
    )
    (net (code "50") (name "R-") (class "Default")
      (node (ref "C4") (pin "2") (pinfunction "2_2") (pintype "passive"))
      (node (ref "C5") (pin "2") (pinfunction "2_2") (pintype "passive"))
      (node (ref "P3") (pin "1") (pinfunction "1_1") (pintype "passive"))
      (node (ref "U2") (pin "1") (pintype "passive"))
      (node (ref "U7") (pin "5") (pinfunction "VW/RW_5") (pintype "passive"))
    )
    (net (code "51") (name "V_5V") (class "Default")
      (node (ref "C13") (pin "1") (pinfunction "1_1") (pintype "passive"))
      (node (ref "C19") (pin "1") (pinfunction "1_1") (pintype "passive"))
      (node (ref "C2") (pin "1") (pinfunction "1_1") (pintype "passive"))
      (node (ref "C3") (pin "1") (pinfunction "1_1") (pintype "passive"))
      (node (ref "D1") (pin "K") (pinfunction "K_K") (pintype "passive"))
      (node (ref "J2") (pin "1") (pinfunction "1_1") (pintype "passive"))
      (node (ref "J3") (pin "1") (pinfunction "1_1") (pintype "passive"))
      (node (ref "Q5") (pin "S") (pinfunction "S_S") (pintype "input"))
      (node (ref "R25") (pin "1") (pintype "passive"))
      (node (ref "R5") (pin "1") (pintype "passive"))
      (node (ref "U5") (pin "3") (pinfunction "VIN_3") (pintype "passive"))
      (node (ref "U7") (pin "8") (pinfunction "VCC_8") (pintype "passive"))
    )
    (net (code "52") (name "V_BAT") (class "Default")
      (node (ref "C16") (pin "2") (pinfunction "2_2") (pintype "passive"))
      (node (ref "J1") (pin "1") (pinfunction "1_1") (pintype "passive"))
      (node (ref "SW1") (pin "2") (pinfunction "2_2") (pintype "passive"))
      (node (ref "U6") (pin "5") (pinfunction "BAT_5") (pintype "passive"))
    )
    (net (code "53") (name "V_IN") (class "Default")
      (node (ref "C14") (pin "2") (pinfunction "2_2") (pintype "passive"))
      (node (ref "C7") (pin "2") (pinfunction "2_2") (pintype "passive"))
      (node (ref "C8") (pin "2") (pinfunction "2_2") (pintype "passive"))
      (node (ref "D5") (pin "1") (pinfunction "1_1") (pintype "passive"))
      (node (ref "D6") (pin "1") (pinfunction "1_1") (pintype "passive"))
      (node (ref "R13") (pin "1") (pintype "passive"))
      (node (ref "R17") (pin "1") (pintype "passive"))
      (node (ref "U3") (pin "5") (pinfunction "VCC_5") (pintype "passive"))
      (node (ref "U6") (pin "4") (pinfunction "VCC_4") (pintype "passive"))
      (node (ref "U6") (pin "8") (pinfunction "CE_8") (pintype "passive"))
    )
    (net (code "54") (name "unconnected-(P1-ID-Pad4)") (class "Default")
      (node (ref "P1") (pin "4") (pinfunction "ID_4") (pintype "passive"))
    )
    (net (code "55") (name "unconnected-(Q1-G-Pad1)") (class "Default")
      (node (ref "Q1") (pin "1") (pinfunction "G_1") (pintype "passive"))
    )
    (net (code "56") (name "unconnected-(R3-Pad2)") (class "Default")
      (node (ref "R3") (pin "2") (pintype "passive"))
    )
    (net (code "57") (name "unconnected-(SW1-Pad1)") (class "Default")
      (node (ref "SW1") (pin "1") (pinfunction "1_1") (pintype "passive+no_connect"))
    )
    (net (code "58") (name "unconnected-(U3-RTS#-Pad4)") (class "Default")
      (node (ref "U3") (pin "4") (pinfunction "RTS#_4") (pintype "passive"))
    )
    (net (code "59") (name "unconnected-(U4-ALERT-Pad3)") (class "Default")
      (node (ref "U4") (pin "3") (pinfunction "ALERT_3") (pintype "passive"))
    )
    (net (code "60") (name "unconnected-(U7-VL{slash}RL-Pad6)") (class "Default")
      (node (ref "U7") (pin "6") (pinfunction "VL/RL_6") (pintype "passive"))
    )
    (net (code "61") (name "unconnected-(U8-Pad1)") (class "Default")
      (node (ref "U8") (pin "1") (pinfunction "1_1") (pintype "passive+no_connect"))
    )
    (net (code "62") (name "unconnected-(U8-Pad3)") (class "Default")
      (node (ref "U8") (pin "3") (pinfunction "3_3") (pintype "passive+no_connect"))
    )
    (net (code "63") (name "unconnected-(U8-Pad5)") (class "Default")
      (node (ref "U8") (pin "5") (pinfunction "5_5") (pintype "passive+no_connect"))
    )
    (net (code "64") (name "unconnected-(U8-Pad6)") (class "Default")
      (node (ref "U8") (pin "6") (pinfunction "6_6") (pintype "passive+no_connect"))
    )
    (net (code "65") (name "unconnected-(U8-Pad7)") (class "Default")
      (node (ref "U8") (pin "7") (pinfunction "7_7") (pintype "passive+no_connect"))
    )
    (net (code "66") (name "unconnected-(U8-Pad8)") (class "Default")
      (node (ref "U8") (pin "8") (pinfunction "8_8") (pintype "passive+no_connect"))
    )
    (net (code "67") (name "unconnected-(U8-Pad9)") (class "Default")
      (node (ref "U8") (pin "9") (pinfunction "9_9") (pintype "passive+no_connect"))
    )
    (net (code "68") (name "unconnected-(U8-Pad10)") (class "Default")
      (node (ref "U8") (pin "10") (pinfunction "10_10") (pintype "passive+no_connect"))
    )
    (net (code "69") (name "unconnected-(U8-Pad11)") (class "Default")
      (node (ref "U8") (pin "11") (pinfunction "11_11") (pintype "passive+no_connect"))
    )
    (net (code "70") (name "unconnected-(U8-Pad12)") (class "Default")
      (node (ref "U8") (pin "12") (pinfunction "12_12") (pintype "passive+no_connect"))
    )
    (net (code "71") (name "unconnected-(U8-Pad17)") (class "Default")
      (node (ref "U8") (pin "17") (pinfunction "17_17") (pintype "passive+no_connect"))
    )
    (net (code "72") (name "unconnected-(U8-Pad19)") (class "Default")
      (node (ref "U8") (pin "19") (pinfunction "19_19") (pintype "passive+no_connect"))
    )
    (net (code "73") (name "unconnected-(U8-Pad20)") (class "Default")
      (node (ref "U8") (pin "20") (pinfunction "20_20") (pintype "passive+no_connect"))
    )
    (net (code "74") (name "unconnected-(U8-Pad21)") (class "Default")
      (node (ref "U8") (pin "21") (pinfunction "21_21") (pintype "passive+no_connect"))
    )
    (net (code "75") (name "unconnected-(U9-P3.2{slash}SCL-Pad13)") (class "Default")
      (node (ref "U9") (pin "13") (pinfunction "P3.2/SCL_13") (pintype "passive"))
    )
    (net (code "76") (name "unconnected-(U9-P3.5{slash}CCP0_2-Pad16)") (class "Default")
      (node (ref "U9") (pin "16") (pinfunction "P3.5/CCP0_2_16") (pintype "passive"))
    )
  )
)
